# Main.net
KiCad netlist of a schematic drawn in Altium Designer
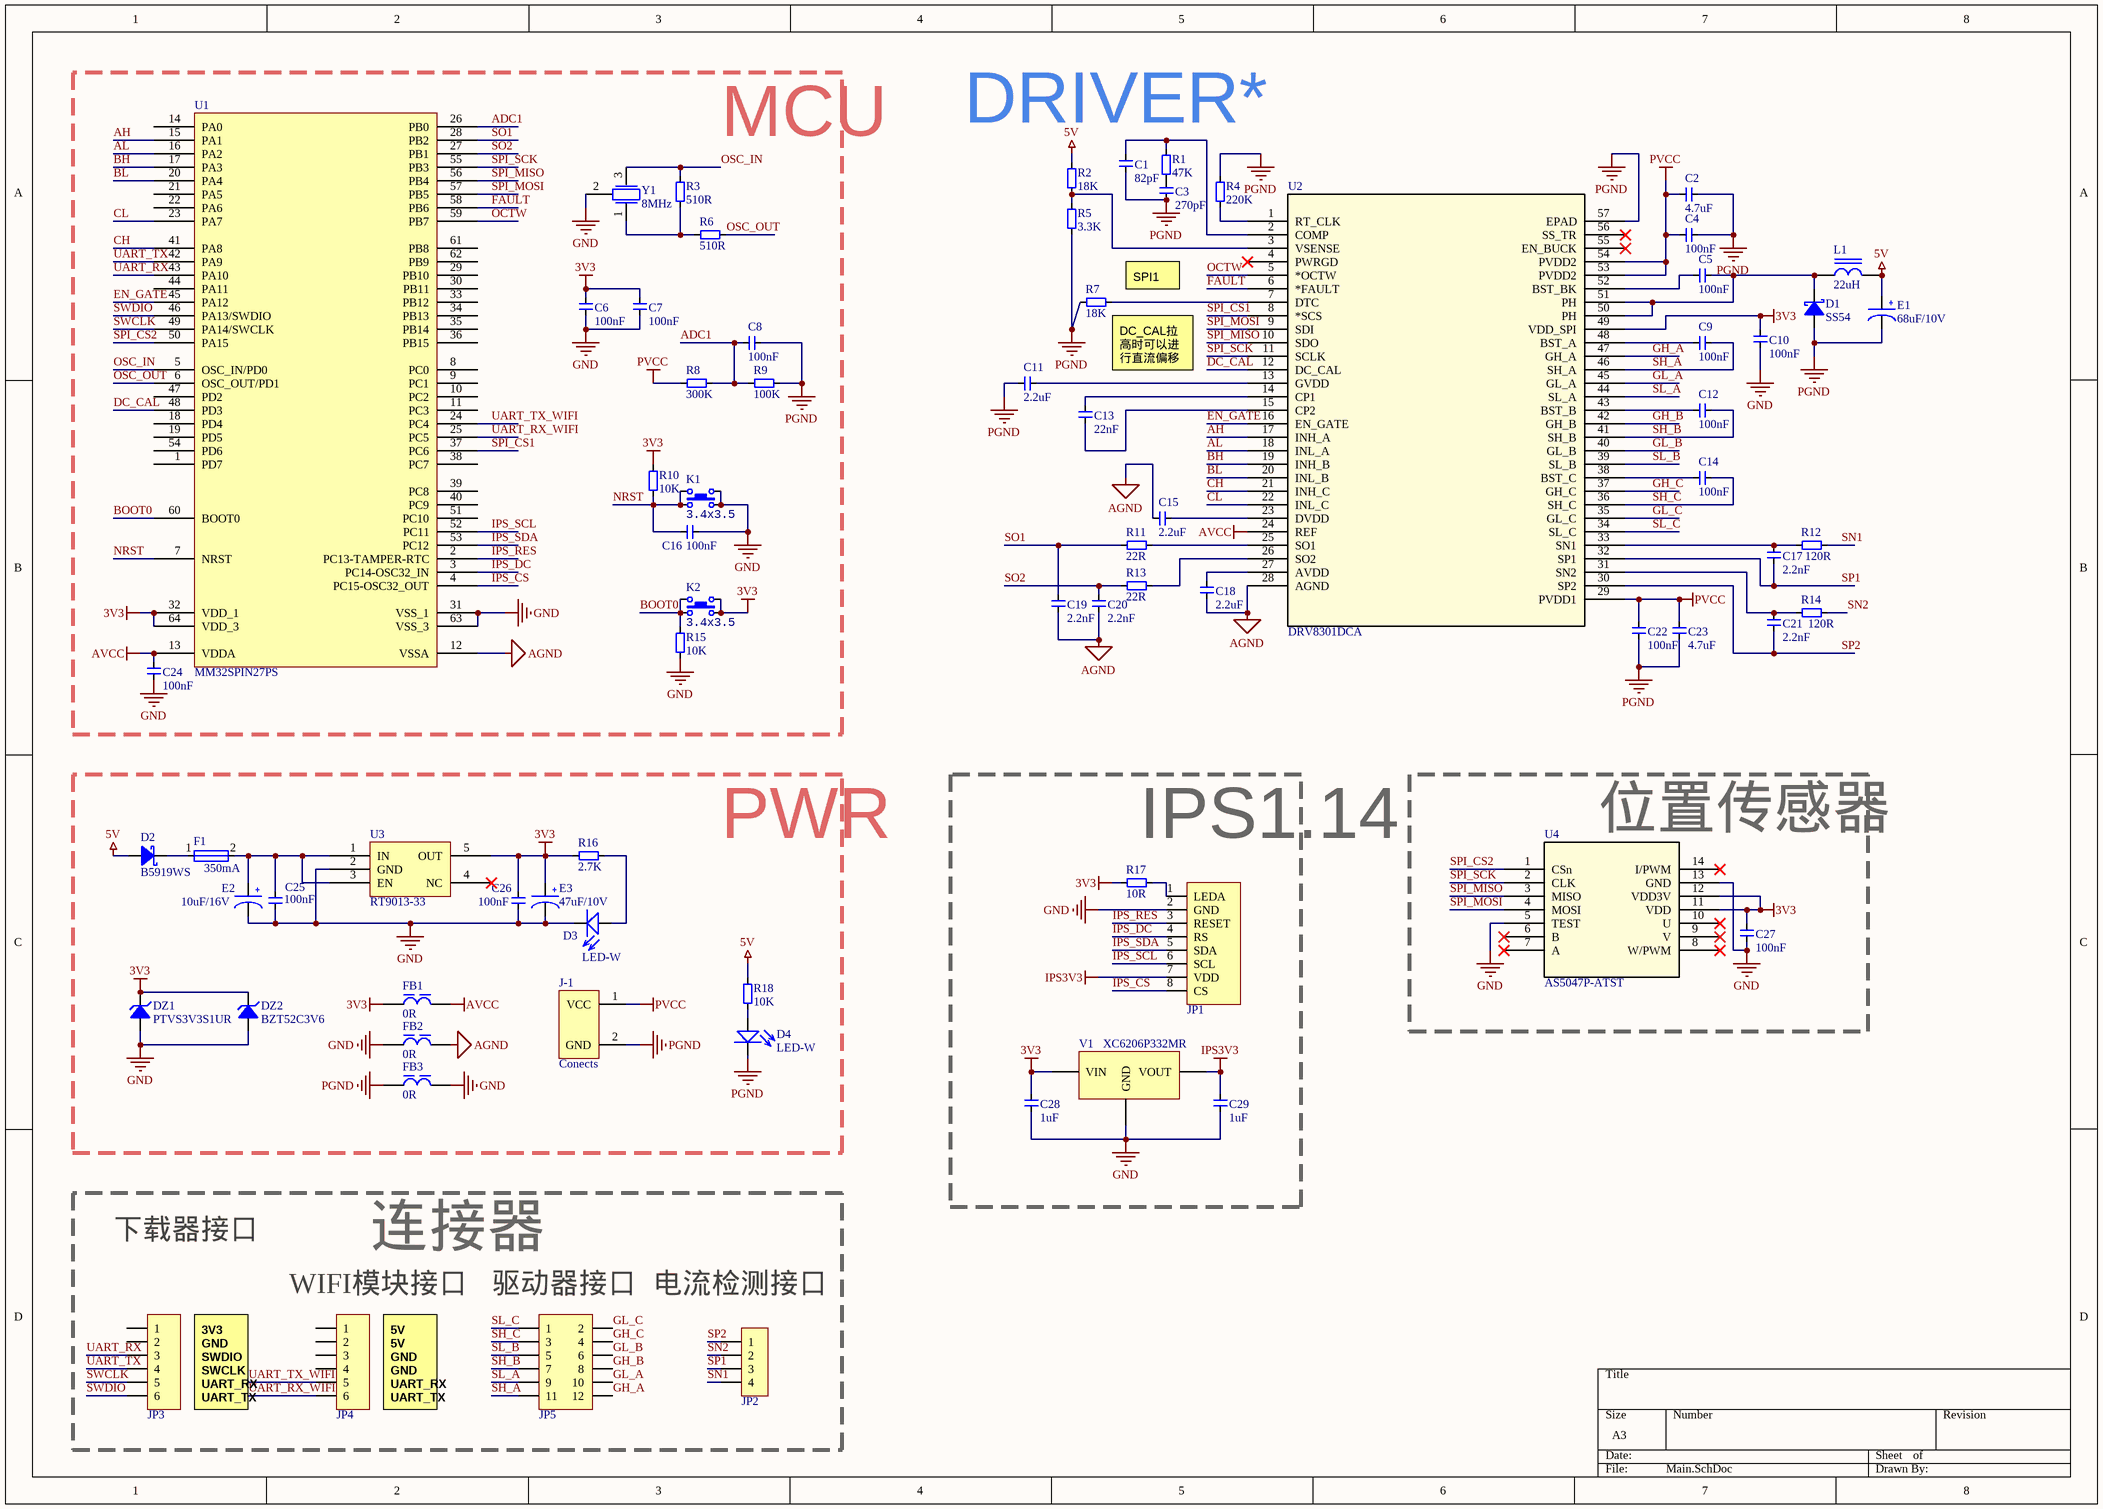
[diagram p0: Main.SchDoc]

(export (version "E")
  (design (tool "Eeschema 10.0.6"))
  (components
    (comp (ref "C1")
      (value "82pF")
      (footprint "C0402_L")
      (description "电容 ¦ 陶瓷电容")
      (fields (field (name "版权归属") "源创客"))
      (libsource (lib "total_lib") (part "C"))
    )
    (comp (ref "C2")
      (value "4.7uF")
      (footprint "C0603_L")
      (description "电容 ¦ 陶瓷电容")
      (fields (field (name "版权归属") "源创客"))
      (libsource (lib "total_lib") (part "C"))
    )
    (comp (ref "C3")
      (value "270pF")
      (footprint "C0402_L")
      (description "电容 ¦ 陶瓷电容")
      (fields (field (name "版权归属") "源创客"))
      (libsource (lib "total_lib") (part "C"))
    )
    (comp (ref "C4")
      (value "100nF")
      (footprint "C0402_L")
      (description "电容 ¦ 陶瓷电容")
      (fields (field (name "版权归属") "源创客"))
      (libsource (lib "total_lib") (part "C"))
    )
    (comp (ref "C5")
      (value "100nF")
      (footprint "C0402_L")
      (description "电容 ¦ 陶瓷电容")
      (fields (field (name "版权归属") "源创客"))
      (libsource (lib "total_lib") (part "C"))
    )
    (comp (ref "C6")
      (value "100nF")
      (footprint "C0402_L")
      (description "电容 ¦ 陶瓷电容")
      (fields (field (name "版权归属") "源创客"))
      (libsource (lib "total_lib") (part "C"))
    )
    (comp (ref "C7")
      (value "100nF")
      (footprint "C0402_L")
      (description "电容 ¦ 陶瓷电容")
      (fields (field (name "版权归属") "源创客"))
      (libsource (lib "total_lib") (part "C"))
    )
    (comp (ref "C8")
      (value "100nF")
      (footprint "C0402_L")
      (description "电容 ¦ 陶瓷电容")
      (fields (field (name "版权归属") "源创客"))
      (libsource (lib "total_lib") (part "C"))
    )
    (comp (ref "C9")
      (value "100nF")
      (footprint "C0402_L")
      (description "电容 ¦ 陶瓷电容")
      (fields (field (name "版权归属") "源创客"))
      (libsource (lib "total_lib") (part "C"))
    )
    (comp (ref "C10")
      (value "100nF")
      (footprint "C0402_L")
      (description "电容 ¦ 陶瓷电容")
      (fields (field (name "版权归属") "源创客"))
      (libsource (lib "total_lib") (part "C"))
    )
    (comp (ref "C11")
      (value "2.2uF")
      (footprint "C0402_L")
      (description "电容 ¦ 陶瓷电容")
      (fields (field (name "版权归属") "源创客"))
      (libsource (lib "total_lib") (part "C"))
    )
    (comp (ref "C12")
      (value "100nF")
      (footprint "C0402_L")
      (description "电容 ¦ 陶瓷电容")
      (fields (field (name "版权归属") "源创客"))
      (libsource (lib "total_lib") (part "C"))
    )
    (comp (ref "C13")
      (value "22nF")
      (footprint "C0402_L")
      (description "电容 ¦ 陶瓷电容")
      (fields (field (name "版权归属") "源创客"))
      (libsource (lib "total_lib") (part "C"))
    )
    (comp (ref "C14")
      (value "100nF")
      (footprint "C0402_L")
      (description "电容 ¦ 陶瓷电容")
      (fields (field (name "版权归属") "源创客"))
      (libsource (lib "total_lib") (part "C"))
    )
    (comp (ref "C15")
      (value "2.2uF")
      (footprint "C0402_L")
      (description "电容 ¦ 陶瓷电容")
      (fields (field (name "版权归属") "源创客"))
      (libsource (lib "total_lib") (part "C"))
    )
    (comp (ref "C16")
      (value "100nF")
      (footprint "C0402_L")
      (description "电容 ¦ 陶瓷电容")
      (fields (field (name "版权归属") "源创客"))
      (libsource (lib "total_lib") (part "C"))
    )
    (comp (ref "C17")
      (value "2.2nF")
      (footprint "C0402_L")
      (description "电容 ¦ 陶瓷电容")
      (fields (field (name "版权归属") "源创客"))
      (libsource (lib "total_lib") (part "C"))
    )
    (comp (ref "C18")
      (value "2.2uF")
      (footprint "C0402_L")
      (description "电容 ¦ 陶瓷电容")
      (fields (field (name "版权归属") "源创客"))
      (libsource (lib "total_lib") (part "C"))
    )
    (comp (ref "C19")
      (value "2.2nF")
      (footprint "C0402_L")
      (description "电容 ¦ 陶瓷电容")
      (fields (field (name "版权归属") "源创客"))
      (libsource (lib "total_lib") (part "C"))
    )
    (comp (ref "C20")
      (value "2.2nF")
      (footprint "C0402_L")
      (description "电容 ¦ 陶瓷电容")
      (fields (field (name "版权归属") "源创客"))
      (libsource (lib "total_lib") (part "C"))
    )
    (comp (ref "C21")
      (value "2.2nF")
      (footprint "C0402_L")
      (description "电容 ¦ 陶瓷电容")
      (fields (field (name "版权归属") "源创客"))
      (libsource (lib "total_lib") (part "C"))
    )
    (comp (ref "C22")
      (value "100nF")
      (footprint "C0402_L")
      (description "电容 ¦ 陶瓷电容")
      (fields (field (name "版权归属") "源创客"))
      (libsource (lib "total_lib") (part "C"))
    )
    (comp (ref "C23")
      (value "4.7uF")
      (footprint "C0603_L")
      (description "电容 ¦ 陶瓷电容")
      (fields (field (name "版权归属") "源创客"))
      (libsource (lib "total_lib") (part "C"))
    )
    (comp (ref "C24")
      (value "100nF")
      (footprint "C0402_L")
      (description "电容 ¦ 陶瓷电容")
      (fields (field (name "版权归属") "源创客"))
      (libsource (lib "total_lib") (part "C"))
    )
    (comp (ref "C25")
      (value "100nF")
      (footprint "C0402_L")
      (description "电容 ¦ 陶瓷电容")
      (fields (field (name "版权归属") "源创客"))
      (libsource (lib "total_lib") (part "C"))
    )
    (comp (ref "C26")
      (value "100nF")
      (footprint "C0402_L")
      (description "电容 ¦ 陶瓷电容")
      (fields (field (name "版权归属") "源创客"))
      (libsource (lib "total_lib") (part "C"))
    )
    (comp (ref "C27")
      (value "100nF")
      (footprint "C0402_L")
      (description "电容 ¦ 陶瓷电容")
      (fields (field (name "版权归属") "源创客"))
      (libsource (lib "total_lib") (part "C"))
    )
    (comp (ref "C28")
      (value "1uF")
      (footprint "C0402_L")
      (description "电容 ¦ 陶瓷电容")
      (fields (field (name "版权归属") "源创客"))
      (libsource (lib "total_lib") (part "C"))
    )
    (comp (ref "C29")
      (value "1uF")
      (footprint "C0402_L")
      (description "电容 ¦ 陶瓷电容")
      (fields (field (name "版权归属") "源创客"))
      (libsource (lib "total_lib") (part "C"))
    )
    (comp (ref "D1")
      (value "SS54")
      (footprint "SMB")
      (description "二极管 ¦ 肖特基二极管")
      (libsource (lib "total_lib") (part "SS54"))
    )
    (comp (ref "D2")
      (value "B5919WS")
      (footprint "SOD-323")
      (description "二极管 ¦ 肖特基二极管")
      (libsource (lib "total_lib") (part "1N5819"))
    )
    (comp (ref "D3")
      (value "LED-W")
      (footprint "LED 0402")
      (description "二极管 ¦ 白色LED")
      (libsource (lib "total_lib") (part "LED-White"))
    )
    (comp (ref "D4")
      (value "LED-W")
      (footprint "LED 0402")
      (description "二极管 ¦ 白色LED")
      (libsource (lib "total_lib") (part "LED-White"))
    )
    (comp (ref "DZ1")
      (value "PTVS3V3S1UR")
      (footprint "SOD-123")
      (description "二极管 ¦ 齐纳二极管")
      (libsource (lib "total_lib") (part "PTVS3V3S1UR"))
    )
    (comp (ref "DZ2")
      (value "BZT52C3V6")
      (footprint "SOD-123")
      (description "二极管 ¦ 齐纳二极管")
      (libsource (lib "total_lib") (part "BZT52C3V6"))
    )
    (comp (ref "E1")
      (value "68uF/10V")
      (footprint "CE D(6.3*5.4)")
      (description "电容 ¦ 电解电容")
      (fields (field (name "版权归属") "源创客"))
      (libsource (lib "total_lib") (part "C-CM"))
    )
    (comp (ref "E2")
      (value "10uF/16V")
      (footprint "C_3528")
      (description "电容 ¦ 钽电容")
      (fields (field (name "版权归属") "源创客"))
      (libsource (lib "total_lib") (part "C-CD"))
    )
    (comp (ref "E3")
      (value "47uF/10V")
      (footprint "C_3528")
      (description "电容 ¦ 钽电容")
      (fields (field (name "版权归属") "源创客"))
      (libsource (lib "total_lib") (part "C-CD"))
    )
    (comp (ref "F1")
      (value "350mA")
      (footprint "R0805_L")
      (description "可复位保险丝")
      (libsource (lib "total_lib") (part "FUSE"))
    )
    (comp (ref "FB1")
      (value "0R")
      (footprint "R0603_L")
      (description "磁珠")
      (libsource (lib "total_lib") (part "FB"))
    )
    (comp (ref "FB2")
      (value "0R")
      (footprint "R0603_L")
      (description "磁珠")
      (libsource (lib "total_lib") (part "FB"))
    )
    (comp (ref "FB3")
      (value "0R")
      (footprint "R1206_L")
      (description "磁珠")
      (libsource (lib "total_lib") (part "FB"))
    )
    (comp (ref "J-1")
      (value "Conects")
      (footprint "connecter-PWR")
      (description "插接件 ¦ 电源接口")
      (fields (field (name "版权归属") "源创客"))
      (libsource (lib "total_lib") (part "Conects"))
    )
    (comp (ref "JP1")
      (value "IPS1.14")
      (footprint "IPS1.14 FPC0.5 2H-WS-8P")
      (description "显示屏 ¦ 1.14寸液晶显示屏")
      (fields (field (name "版权归属") "源创客"))
      (libsource (lib "total_lib") (part "IPS1.14"))
    )
    (comp (ref "JP2")
      (value "HDR-1X4")
      (footprint "connecter-stamps-4p")
      (description "插接件 ¦ 4P接插件")
      (libsource (lib "total_lib") (part "Header 4"))
    )
    (comp (ref "JP3")
      (value "CON-6P")
      (footprint "SH1.0-6P")
      (description "插接件 ¦ SH系列")
      (libsource (lib "total_lib") (part "SH1.0-6P"))
    )
    (comp (ref "JP4")
      (value "CON-6P")
      (footprint "SH1.0-6P")
      (description "插接件 ¦ SH系列")
      (libsource (lib "total_lib") (part "SH1.0-6P"))
    )
    (comp (ref "JP5")
      (value "Header 6X2")
      (footprint "connecter-stamps-12p")
      (description "插接件 ¦ 6*2P接插件")
      (libsource (lib "total_lib") (part "Header  6X2"))
    )
    (comp (ref "K1")
      (value "3.4x3.5")
      (footprint "ButtonTACT_3.5*3.55_90")
      (description "轻触开关 ¦ 3.4x3.5四脚")
      (fields (field (name "Comment") "TACT 4P"))
      (libsource (lib "total_lib") (part "ButtonTACT"))
    )
    (comp (ref "K2")
      (value "3.4x3.5")
      (footprint "ButtonTACT_3.5*3.55_90")
      (description "轻触开关 ¦ 3.4x3.5四脚")
      (fields (field (name "Comment") "TACT 4P"))
      (libsource (lib "total_lib") (part "ButtonTACT"))
    )
    (comp (ref "L1")
      (value "22uH")
      (footprint "NR5040")
      (description "电感 ¦ 贴片功率电感")
      (fields (field (name "版权归属") "源创客"))
      (libsource (lib "total_lib") (part "L-CD"))
    )
    (comp (ref "R1")
      (value "47K")
      (footprint "R0402_L")
      (description "电阻 ¦ 贴片电阻")
      (fields (field (name "版权归属") "源创客"))
      (libsource (lib "total_lib") (part "R"))
    )
    (comp (ref "R2")
      (value "18K")
      (footprint "R0402_L")
      (description "电阻 ¦ 贴片电阻")
      (fields (field (name "版权归属") "源创客"))
      (libsource (lib "total_lib") (part "R"))
    )
    (comp (ref "R3")
      (value "510R")
      (footprint "R0402_L")
      (description "电阻 ¦ 贴片电阻")
      (fields (field (name "版权归属") "源创客"))
      (libsource (lib "total_lib") (part "R"))
    )
    (comp (ref "R4")
      (value "220K")
      (footprint "R0402_L")
      (description "电阻 ¦ 贴片电阻")
      (fields (field (name "版权归属") "源创客"))
      (libsource (lib "total_lib") (part "R"))
    )
    (comp (ref "R5")
      (value "3.3K")
      (footprint "R0402_L")
      (description "电阻 ¦ 贴片电阻")
      (fields (field (name "版权归属") "源创客"))
      (libsource (lib "total_lib") (part "R"))
    )
    (comp (ref "R6")
      (value "510R")
      (footprint "R0402_L")
      (description "电阻 ¦ 贴片电阻")
      (fields (field (name "版权归属") "源创客"))
      (libsource (lib "total_lib") (part "R"))
    )
    (comp (ref "R7")
      (value "18K")
      (footprint "R0402_L")
      (description "电阻 ¦ 贴片电阻")
      (fields (field (name "版权归属") "源创客"))
      (libsource (lib "total_lib") (part "R"))
    )
    (comp (ref "R8")
      (value "300K")
      (footprint "R0402_L")
      (description "电阻 ¦ 贴片电阻")
      (fields (field (name "版权归属") "源创客"))
      (libsource (lib "total_lib") (part "R"))
    )
    (comp (ref "R9")
      (value "100K")
      (footprint "R0402_L")
      (description "电阻 ¦ 贴片电阻")
      (fields (field (name "版权归属") "源创客"))
      (libsource (lib "total_lib") (part "R"))
    )
    (comp (ref "R10")
      (value "10K")
      (footprint "R0402_L")
      (description "电阻 ¦ 贴片电阻")
      (fields (field (name "版权归属") "源创客"))
      (libsource (lib "total_lib") (part "R"))
    )
    (comp (ref "R11")
      (value "22R")
      (footprint "R0402_L")
      (description "电阻 ¦ 贴片电阻")
      (fields (field (name "版权归属") "源创客"))
      (libsource (lib "total_lib") (part "R"))
    )
    (comp (ref "R12")
      (value "120R")
      (footprint "R0402_L")
      (description "电阻 ¦ 贴片电阻")
      (fields (field (name "版权归属") "源创客"))
      (libsource (lib "total_lib") (part "R"))
    )
    (comp (ref "R13")
      (value "22R")
      (footprint "R0402_L")
      (description "电阻 ¦ 贴片电阻")
      (fields (field (name "版权归属") "源创客"))
      (libsource (lib "total_lib") (part "R"))
    )
    (comp (ref "R14")
      (value "120R")
      (footprint "R0402_L")
      (description "电阻 ¦ 贴片电阻")
      (fields (field (name "版权归属") "源创客"))
      (libsource (lib "total_lib") (part "R"))
    )
    (comp (ref "R15")
      (value "10K")
      (footprint "R0402_L")
      (description "电阻 ¦ 贴片电阻")
      (fields (field (name "版权归属") "源创客"))
      (libsource (lib "total_lib") (part "R"))
    )
    (comp (ref "R16")
      (value "2.7K")
      (footprint "R0402_L")
      (description "电阻 ¦ 贴片电阻")
      (fields (field (name "版权归属") "源创客"))
      (libsource (lib "total_lib") (part "R"))
    )
    (comp (ref "R17")
      (value "10R")
      (footprint "R0402_L")
      (description "电阻 ¦ 贴片电阻")
      (fields (field (name "版权归属") "源创客"))
      (libsource (lib "total_lib") (part "R"))
    )
    (comp (ref "R18")
      (value "10K")
      (footprint "R0402_L")
      (description "电阻 ¦ 贴片电阻")
      (fields (field (name "版权归属") "源创客"))
      (libsource (lib "total_lib") (part "R"))
    )
    (comp (ref "U1")
      (value "MM32SPIN27PS")
      (footprint "LQFP64 10x10_L")
      (description "MCU")
      (libsource (lib "total_lib") (part "MM32SPIN27PS"))
    )
    (comp (ref "U2")
      (value "DRV8301DCA")
      (footprint "DCA56_6P35X3P61")
      (description "No Description Available")
      (fields (field (name "COPYRIGHT") "Copyright (C) 2021 Ultra Librarian. All rights reserved."))
      (libsource (lib "total_lib") (part "DRV8301DCA"))
    )
    (comp (ref "U3")
      (value "RT9013-33")
      (footprint "SOT23-5")
      (description "IC ¦ 低压线性稳压器")
      (libsource (lib "total_lib") (part "RT9013-33"))
    )
    (comp (ref "U4")
      (value "AS5047P-ATST")
      (footprint "TSSOP-14_AMS-L")
      (description "No Description Available")
      (fields (field (name "COPYRIGHT") "Copyright (C) 2022 Ultra Librarian. All rights reserved."))
      (libsource (lib "total_lib") (part "AS5047P-ATST"))
    )
    (comp (ref "V1")
      (value "XC6206P332MR")
      (footprint "SOT23")
      (description "IC ¦ 低压线性稳压芯片")
      (fields (field (name "版权归属") "源创客"))
      (libsource (lib "total_lib") (part "XC6206P332MR"))
    )
    (comp (ref "Y1")
      (value "8MHz")
      (footprint "晶振-3P")
      (description "晶振 ¦ 村田贴片")
      (libsource (lib "total_lib") (part "晶振-3Pin"))
    )
  )
  (nets
    (net (code "1") (name "/ADC1") (class "Default")
      (node (ref "C8") (pin "2") (pinfunction "2_2") (pintype "passive"))
      (node (ref "R8") (pin "2") (pinfunction "2_2") (pintype "passive"))
      (node (ref "R9") (pin "1") (pinfunction "1_1") (pintype "passive"))
      (node (ref "U1") (pin "26") (pinfunction "PB0_26") (pintype "passive"))
    )
    (net (code "2") (name "/AH") (class "Default")
      (node (ref "U1") (pin "15") (pinfunction "PA1_15") (pintype "passive"))
      (node (ref "U2") (pin "17") (pinfunction "INH_A_17") (pintype "passive"))
    )
    (net (code "3") (name "/AL") (class "Default")
      (node (ref "U1") (pin "16") (pinfunction "PA2_16") (pintype "passive"))
      (node (ref "U2") (pin "18") (pinfunction "INL_A_18") (pintype "passive"))
    )
    (net (code "4") (name "/BH") (class "Default")
      (node (ref "U1") (pin "17") (pinfunction "PA3_17") (pintype "passive"))
      (node (ref "U2") (pin "19") (pinfunction "INH_B_19") (pintype "passive"))
    )
    (net (code "5") (name "/BL") (class "Default")
      (node (ref "U1") (pin "20") (pinfunction "PA4_20") (pintype "passive"))
      (node (ref "U2") (pin "20") (pinfunction "INL_B_20") (pintype "passive"))
    )
    (net (code "6") (name "/BOOT0") (class "Default")
      (node (ref "K2") (pin "1") (pinfunction "1_1") (pintype "passive"))
      (node (ref "K2") (pin "3") (pinfunction "3_3") (pintype "passive"))
      (node (ref "R15") (pin "1") (pinfunction "1_1") (pintype "passive"))
      (node (ref "U1") (pin "60") (pinfunction "BOOT0_60") (pintype "passive"))
    )
    (net (code "7") (name "/CH") (class "Default")
      (node (ref "U1") (pin "41") (pinfunction "PA8_41") (pintype "passive"))
      (node (ref "U2") (pin "21") (pinfunction "INH_C_21") (pintype "passive"))
    )
    (net (code "8") (name "/CL") (class "Default")
      (node (ref "U1") (pin "23") (pinfunction "PA7_23") (pintype "passive"))
      (node (ref "U2") (pin "22") (pinfunction "INL_C_22") (pintype "passive"))
    )
    (net (code "9") (name "/DC_CAL") (class "Default")
      (node (ref "U1") (pin "48") (pinfunction "PD3_48") (pintype "passive"))
      (node (ref "U2") (pin "12") (pinfunction "DC_CAL_12") (pintype "passive"))
    )
    (net (code "10") (name "/EN_GATE") (class "Default")
      (node (ref "U1") (pin "45") (pinfunction "PA12_45") (pintype "passive"))
      (node (ref "U2") (pin "16") (pinfunction "EN_GATE_16") (pintype "passive"))
    )
    (net (code "11") (name "/FAULT") (class "Default")
      (node (ref "U1") (pin "58") (pinfunction "PB6_58") (pintype "passive"))
      (node (ref "U2") (pin "6") (pinfunction "*FAULT_6") (pintype "passive"))
    )
    (net (code "12") (name "/GH_A") (class "Default")
      (node (ref "JP5") (pin "12") (pinfunction "12_12") (pintype "passive"))
      (node (ref "U2") (pin "47") (pinfunction "GH_A_47") (pintype "passive"))
    )
    (net (code "13") (name "/GH_B") (class "Default")
      (node (ref "JP5") (pin "8") (pinfunction "8_8") (pintype "passive"))
      (node (ref "U2") (pin "42") (pinfunction "GH_B_42") (pintype "passive"))
    )
    (net (code "14") (name "/GH_C") (class "Default")
      (node (ref "JP5") (pin "4") (pinfunction "4_4") (pintype "passive"))
      (node (ref "U2") (pin "37") (pinfunction "GH_C_37") (pintype "passive"))
    )
    (net (code "15") (name "/GL_A") (class "Default")
      (node (ref "JP5") (pin "10") (pinfunction "10_10") (pintype "passive"))
      (node (ref "U2") (pin "45") (pinfunction "GL_A_45") (pintype "passive"))
    )
    (net (code "16") (name "/GL_B") (class "Default")
      (node (ref "JP5") (pin "6") (pinfunction "6_6") (pintype "passive"))
      (node (ref "U2") (pin "40") (pinfunction "GL_B_40") (pintype "passive"))
    )
    (net (code "17") (name "/GL_C") (class "Default")
      (node (ref "JP5") (pin "2") (pinfunction "2_2") (pintype "passive"))
      (node (ref "U2") (pin "35") (pinfunction "GL_C_35") (pintype "passive"))
    )
    (net (code "18") (name "/IPS_CS") (class "Default")
      (node (ref "JP1") (pin "8") (pinfunction "CS_8") (pintype "passive"))
      (node (ref "U1") (pin "4") (pinfunction "PC15-OSC32_OUT_4") (pintype "passive"))
    )
    (net (code "19") (name "/IPS_DC") (class "Default")
      (node (ref "JP1") (pin "4") (pinfunction "RS_4") (pintype "passive"))
      (node (ref "U1") (pin "3") (pinfunction "PC14-OSC32_IN_3") (pintype "passive"))
    )
    (net (code "20") (name "/IPS_RES") (class "Default")
      (node (ref "JP1") (pin "3") (pinfunction "RESET_3") (pintype "passive"))
      (node (ref "U1") (pin "2") (pinfunction "PC13-TAMPER-RTC_2") (pintype "passive"))
    )
    (net (code "21") (name "/IPS_SCL") (class "Default")
      (node (ref "JP1") (pin "6") (pinfunction "SCL_6") (pintype "passive"))
      (node (ref "U1") (pin "52") (pinfunction "PC11_52") (pintype "passive"))
    )
    (net (code "22") (name "/IPS_SDA") (class "Default")
      (node (ref "JP1") (pin "5") (pinfunction "SDA_5") (pintype "passive"))
      (node (ref "U1") (pin "53") (pinfunction "PC12_53") (pintype "passive"))
    )
    (net (code "23") (name "/NRST") (class "Default")
      (node (ref "C16") (pin "1") (pinfunction "1_1") (pintype "passive"))
      (node (ref "K1") (pin "1") (pinfunction "1_1") (pintype "passive"))
      (node (ref "K1") (pin "3") (pinfunction "3_3") (pintype "passive"))
      (node (ref "R10") (pin "2") (pinfunction "2_2") (pintype "passive"))
      (node (ref "U1") (pin "7") (pinfunction "NRST_7") (pintype "passive"))
    )
    (net (code "24") (name "/OCTW") (class "Default")
      (node (ref "U1") (pin "59") (pinfunction "PB7_59") (pintype "passive"))
      (node (ref "U2") (pin "5") (pinfunction "*OCTW_5") (pintype "passive"))
    )
    (net (code "25") (name "/OSC_IN") (class "Default")
      (node (ref "R3") (pin "2") (pinfunction "2_2") (pintype "passive"))
      (node (ref "U1") (pin "5") (pinfunction "OSC_IN/PD0_5") (pintype "passive"))
      (node (ref "Y1") (pin "3") (pinfunction "3_3") (pintype "passive"))
    )
    (net (code "26") (name "/OSC_OUT") (class "Default")
      (node (ref "R6") (pin "2") (pinfunction "2_2") (pintype "passive"))
      (node (ref "U1") (pin "6") (pinfunction "OSC_OUT/PD1_6") (pintype "passive"))
    )
    (net (code "27") (name "/SH_A") (class "Default")
      (node (ref "C9") (pin "1") (pinfunction "1_1") (pintype "passive"))
      (node (ref "JP5") (pin "11") (pinfunction "11_11") (pintype "passive"))
      (node (ref "U2") (pin "46") (pinfunction "SH_A_46") (pintype "passive"))
    )
    (net (code "28") (name "/SH_B") (class "Default")
      (node (ref "C12") (pin "1") (pinfunction "1_1") (pintype "passive"))
      (node (ref "JP5") (pin "7") (pinfunction "7_7") (pintype "passive"))
      (node (ref "U2") (pin "41") (pinfunction "SH_B_41") (pintype "passive"))
    )
    (net (code "29") (name "/SH_C") (class "Default")
      (node (ref "C14") (pin "1") (pinfunction "1_1") (pintype "passive"))
      (node (ref "JP5") (pin "3") (pinfunction "3_3") (pintype "passive"))
      (node (ref "U2") (pin "36") (pinfunction "SH_C_36") (pintype "passive"))
    )
    (net (code "30") (name "/SL_A") (class "Default")
      (node (ref "JP5") (pin "9") (pinfunction "9_9") (pintype "passive"))
      (node (ref "U2") (pin "44") (pinfunction "SL_A_44") (pintype "passive"))
    )
    (net (code "31") (name "/SL_B") (class "Default")
      (node (ref "JP5") (pin "5") (pinfunction "5_5") (pintype "passive"))
      (node (ref "U2") (pin "39") (pinfunction "SL_B_39") (pintype "passive"))
    )
    (net (code "32") (name "/SL_C") (class "Default")
      (node (ref "JP5") (pin "1") (pinfunction "1_1") (pintype "passive"))
      (node (ref "U2") (pin "34") (pinfunction "SL_C_34") (pintype "passive"))
    )
    (net (code "33") (name "/SN1") (class "Default")
      (node (ref "JP2") (pin "4") (pinfunction "4_4") (pintype "passive"))
      (node (ref "R12") (pin "1") (pinfunction "1_1") (pintype "passive"))
    )
    (net (code "34") (name "/SN2") (class "Default")
      (node (ref "JP2") (pin "2") (pinfunction "2_2") (pintype "passive"))
      (node (ref "R14") (pin "1") (pinfunction "1_1") (pintype "passive"))
    )
    (net (code "35") (name "/SO1") (class "Default")
      (node (ref "C19") (pin "2") (pinfunction "2_2") (pintype "passive"))
      (node (ref "R11") (pin "2") (pinfunction "2_2") (pintype "passive"))
      (node (ref "U1") (pin "28") (pinfunction "PB2_28") (pintype "passive"))
    )
    (net (code "36") (name "/SO2") (class "Default")
      (node (ref "C20") (pin "2") (pinfunction "2_2") (pintype "passive"))
      (node (ref "R13") (pin "2") (pinfunction "2_2") (pintype "passive"))
      (node (ref "U1") (pin "27") (pinfunction "PB1_27") (pintype "passive"))
    )
    (net (code "37") (name "/SP1") (class "Default")
      (node (ref "C17") (pin "1") (pinfunction "1_1") (pintype "passive"))
      (node (ref "JP2") (pin "3") (pinfunction "3_3") (pintype "passive"))
      (node (ref "U2") (pin "32") (pinfunction "SP1_32") (pintype "passive"))
    )
    (net (code "38") (name "/SP2") (class "Default")
      (node (ref "C21") (pin "1") (pinfunction "1_1") (pintype "passive"))
      (node (ref "JP2") (pin "1") (pinfunction "1_1") (pintype "passive"))
      (node (ref "U2") (pin "30") (pinfunction "SP2_30") (pintype "passive"))
    )
    (net (code "39") (name "/SPI_CS1") (class "Default")
      (node (ref "U1") (pin "37") (pinfunction "PC6_37") (pintype "passive"))
      (node (ref "U2") (pin "8") (pinfunction "*SCS_8") (pintype "passive"))
    )
    (net (code "40") (name "/SPI_CS2") (class "Default")
      (node (ref "U1") (pin "50") (pinfunction "PA15_50") (pintype "passive"))
      (node (ref "U4") (pin "1") (pinfunction "CSn_1") (pintype "passive"))
    )
    (net (code "41") (name "/SPI_MISO") (class "Default")
      (node (ref "U1") (pin "56") (pinfunction "PB4_56") (pintype "passive"))
      (node (ref "U2") (pin "10") (pinfunction "SDO_10") (pintype "passive"))
      (node (ref "U4") (pin "3") (pinfunction "MISO_3") (pintype "passive"))
    )
    (net (code "42") (name "/SPI_MOSI") (class "Default")
      (node (ref "U1") (pin "57") (pinfunction "PB5_57") (pintype "passive"))
      (node (ref "U2") (pin "9") (pinfunction "SDI_9") (pintype "passive"))
      (node (ref "U4") (pin "4") (pinfunction "MOSI_4") (pintype "passive"))
    )
    (net (code "43") (name "/SPI_SCK") (class "Default")
      (node (ref "U1") (pin "55") (pinfunction "PB3_55") (pintype "passive"))
      (node (ref "U2") (pin "11") (pinfunction "SCLK_11") (pintype "passive"))
      (node (ref "U4") (pin "2") (pinfunction "CLK_2") (pintype "passive"))
    )
    (net (code "44") (name "/SWCLK") (class "Default")
      (node (ref "JP3") (pin "5") (pinfunction "5_5") (pintype "passive"))
      (node (ref "U1") (pin "49") (pinfunction "PA14/SWCLK_49") (pintype "passive"))
    )
    (net (code "45") (name "/SWDIO") (class "Default")
      (node (ref "JP3") (pin "6") (pinfunction "6_6") (pintype "passive"))
      (node (ref "U1") (pin "46") (pinfunction "PA13/SWDIO_46") (pintype "passive"))
    )
    (net (code "46") (name "/UART_RX") (class "Default")
      (node (ref "JP3") (pin "3") (pinfunction "3_3") (pintype "passive"))
      (node (ref "U1") (pin "43") (pinfunction "PA10_43") (pintype "passive"))
    )
    (net (code "47") (name "/UART_RX_WIFI") (class "Default")
      (node (ref "JP4") (pin "6") (pinfunction "6_6") (pintype "passive"))
      (node (ref "U1") (pin "25") (pinfunction "PC5_25") (pintype "passive"))
    )
    (net (code "48") (name "/UART_TX") (class "Default")
      (node (ref "JP3") (pin "4") (pinfunction "4_4") (pintype "passive"))
      (node (ref "U1") (pin "42") (pinfunction "PA9_42") (pintype "passive"))
    )
    (net (code "49") (name "/UART_TX_WIFI") (class "Default")
      (node (ref "JP4") (pin "5") (pinfunction "5_5") (pintype "passive"))
      (node (ref "U1") (pin "24") (pinfunction "PC4_24") (pintype "passive"))
    )
    (net (code "50") (name "3V3") (class "Default")
      (node (ref "C10") (pin "1") (pinfunction "1_1") (pintype "passive"))
      (node (ref "C26") (pin "1") (pinfunction "1_1") (pintype "passive"))
      (node (ref "C27") (pin "1") (pinfunction "1_1") (pintype "passive"))
      (node (ref "C28") (pin "2") (pinfunction "2_2") (pintype "passive"))
      (node (ref "C6") (pin "2") (pinfunction "2_2") (pintype "passive"))
      (node (ref "C7") (pin "2") (pinfunction "2_2") (pintype "passive"))
      (node (ref "DZ1") (pin "2") (pinfunction "K_2") (pintype "passive"))
      (node (ref "DZ2") (pin "2") (pinfunction "K_2") (pintype "passive"))
      (node (ref "E3") (pin "1") (pinfunction "A_1") (pintype "passive"))
      (node (ref "FB1") (pin "2") (pinfunction "2_2") (pintype "passive"))
      (node (ref "K2") (pin "2") (pinfunction "2_2") (pintype "passive"))
      (node (ref "K2") (pin "4") (pinfunction "4_4") (pintype "passive"))
      (node (ref "R10") (pin "1") (pinfunction "1_1") (pintype "passive"))
      (node (ref "R16") (pin "1") (pinfunction "1_1") (pintype "passive"))
      (node (ref "R17") (pin "2") (pinfunction "2_2") (pintype "passive"))
      (node (ref "U1") (pin "32") (pinfunction "VDD_1_32") (pintype "passive"))
      (node (ref "U1") (pin "64") (pinfunction "VDD_3_64") (pintype "passive"))
      (node (ref "U2") (pin "49") (pinfunction "VDD_SPI_49") (pintype "passive"))
      (node (ref "U3") (pin "5") (pinfunction "OUT_5") (pintype "passive"))
      (node (ref "U4") (pin "11") (pinfunction "VDD_11") (pintype "passive"))
      (node (ref "U4") (pin "12") (pinfunction "VDD3V_12") (pintype "passive"))
      (node (ref "V1") (pin "3") (pinfunction "VIN_3") (pintype "passive"))
    )
    (net (code "51") (name "5V") (class "Default")
      (node (ref "D2") (pin "1") (pinfunction "A_1") (pintype "passive"))
      (node (ref "E1") (pin "1") (pinfunction "A_1") (pintype "passive"))
      (node (ref "L1") (pin "2") (pinfunction "2_2") (pintype "passive"))
      (node (ref "R18") (pin "1") (pinfunction "1_1") (pintype "passive"))
      (node (ref "R2") (pin "2") (pinfunction "2_2") (pintype "passive"))
    )
    (net (code "52") (name "AGND") (class "Default")
      (node (ref "C15") (pin "1") (pinfunction "1_1") (pintype "passive"))
      (node (ref "C18") (pin "1") (pinfunction "1_1") (pintype "passive"))
      (node (ref "C19") (pin "1") (pinfunction "1_1") (pintype "passive"))
      (node (ref "C20") (pin "1") (pinfunction "1_1") (pintype "passive"))
      (node (ref "FB2") (pin "1") (pinfunction "1_1") (pintype "passive"))
      (node (ref "U1") (pin "12") (pinfunction "VSSA_12") (pintype "passive"))
      (node (ref "U2") (pin "28") (pinfunction "AGND_28") (pintype "passive"))
    )
    (net (code "53") (name "AVCC") (class "Default")
      (node (ref "C24") (pin "2") (pinfunction "2_2") (pintype "passive"))
      (node (ref "FB1") (pin "1") (pinfunction "1_1") (pintype "passive"))
      (node (ref "U1") (pin "13") (pinfunction "VDDA_13") (pintype "passive"))
      (node (ref "U2") (pin "24") (pinfunction "REF_24") (pintype "passive"))
    )
    (net (code "54") (name "GND") (class "Default")
      (node (ref "C10") (pin "2") (pinfunction "2_2") (pintype "passive"))
      (node (ref "C16") (pin "2") (pinfunction "2_2") (pintype "passive"))
      (node (ref "C24") (pin "1") (pinfunction "1_1") (pintype "passive"))
      (node (ref "C25") (pin "2") (pinfunction "2_2") (pintype "passive"))
      (node (ref "C26") (pin "2") (pinfunction "2_2") (pintype "passive"))
      (node (ref "C27") (pin "2") (pinfunction "2_2") (pintype "passive"))
      (node (ref "C28") (pin "1") (pinfunction "1_1") (pintype "passive"))
      (node (ref "C29") (pin "1") (pinfunction "1_1") (pintype "passive"))
      (node (ref "C6") (pin "1") (pinfunction "1_1") (pintype "passive"))
      (node (ref "C7") (pin "1") (pinfunction "1_1") (pintype "passive"))
      (node (ref "D3") (pin "2") (pinfunction "1_2") (pintype "passive"))
      (node (ref "DZ1") (pin "1") (pinfunction "A_1") (pintype "passive"))
      (node (ref "DZ2") (pin "1") (pinfunction "A_1") (pintype "passive"))
      (node (ref "E2") (pin "2") (pinfunction "K_2") (pintype "passive"))
      (node (ref "E3") (pin "2") (pinfunction "K_2") (pintype "passive"))
      (node (ref "FB2") (pin "2") (pinfunction "2_2") (pintype "passive"))
      (node (ref "FB3") (pin "1") (pinfunction "1_1") (pintype "passive"))
      (node (ref "JP1") (pin "2") (pinfunction "GND_2") (pintype "passive"))
      (node (ref "K1") (pin "2") (pinfunction "2_2") (pintype "passive"))
      (node (ref "K1") (pin "4") (pinfunction "4_4") (pintype "passive"))
      (node (ref "R15") (pin "2") (pinfunction "2_2") (pintype "passive"))
      (node (ref "U1") (pin "31") (pinfunction "VSS_1_31") (pintype "passive"))
      (node (ref "U1") (pin "63") (pinfunction "VSS_3_63") (pintype "passive"))
      (node (ref "U3") (pin "2") (pinfunction "GND_2") (pintype "passive"))
      (node (ref "U4") (pin "13") (pinfunction "GND_13") (pintype "passive"))
      (node (ref "U4") (pin "5") (pinfunction "TEST_5") (pintype "passive"))
      (node (ref "V1") (pin "1") (pinfunction "GND_1") (pintype "passive"))
      (node (ref "Y1") (pin "2") (pinfunction "2_2") (pintype "passive"))
    )
    (net (code "55") (name "IPS3V3") (class "Default")
      (node (ref "C29") (pin "2") (pinfunction "2_2") (pintype "passive"))
      (node (ref "JP1") (pin "7") (pinfunction "VDD_7") (pintype "passive"))
      (node (ref "V1") (pin "2") (pinfunction "VOUT_2") (pintype "passive"))
    )
    (net (code "56") (name "Net-(C3-Pad2)") (class "Default")
      (node (ref "C3") (pin "2") (pinfunction "2_2") (pintype "passive"))
      (node (ref "R1") (pin "1") (pinfunction "1_1") (pintype "passive"))
    )
    (net (code "57") (name "Net-(D1-K)") (class "Default")
      (node (ref "C5") (pin "1") (pinfunction "1_1") (pintype "passive"))
      (node (ref "D1") (pin "2") (pinfunction "K_2") (pintype "passive"))
      (node (ref "L1") (pin "1") (pinfunction "1_1") (pintype "passive"))
      (node (ref "U2") (pin "50") (pinfunction "PH_50") (pintype "passive"))
      (node (ref "U2") (pin "51") (pinfunction "PH_51") (pintype "passive"))
    )
    (net (code "58") (name "Net-(D2-K)") (class "Default")
      (node (ref "D2") (pin "2") (pinfunction "K_2") (pintype "passive"))
      (node (ref "F1") (pin "1") (pinfunction "116_1") (pintype "passive"))
    )
    (net (code "59") (name "Net-(D3-2)") (class "Default")
      (node (ref "D3") (pin "1") (pinfunction "2_1") (pintype "passive"))
      (node (ref "R16") (pin "2") (pinfunction "2_2") (pintype "passive"))
    )
    (net (code "60") (name "Net-(D4-2)") (class "Default")
      (node (ref "D4") (pin "1") (pinfunction "2_1") (pintype "passive"))
      (node (ref "R18") (pin "2") (pinfunction "2_2") (pintype "passive"))
    )
    (net (code "61") (name "Net-(E2-A)") (class "Default")
      (node (ref "C25") (pin "1") (pinfunction "1_1") (pintype "passive"))
      (node (ref "E2") (pin "1") (pinfunction "A_1") (pintype "passive"))
      (node (ref "F1") (pin "2") (pinfunction "2_2") (pintype "passive"))
      (node (ref "U3") (pin "1") (pinfunction "IN_1") (pintype "passive"))
      (node (ref "U3") (pin "3") (pinfunction "EN_3") (pintype "passive"))
    )
    (net (code "62") (name "Net-(JP1-LEDA)") (class "Default")
      (node (ref "JP1") (pin "1") (pinfunction "LEDA_1") (pintype "passive"))
      (node (ref "R17") (pin "1") (pinfunction "1_1") (pintype "passive"))
    )
    (net (code "63") (name "Net-(R3-Pad1)") (class "Default")
      (node (ref "R3") (pin "1") (pinfunction "1_1") (pintype "passive"))
      (node (ref "R6") (pin "1") (pinfunction "1_1") (pintype "passive"))
      (node (ref "Y1") (pin "1") (pinfunction "1_1") (pintype "passive"))
    )
    (net (code "64") (name "Net-(U2-AVDD)") (class "Default")
      (node (ref "C18") (pin "2") (pinfunction "2_2") (pintype "passive"))
      (node (ref "U2") (pin "27") (pinfunction "AVDD_27") (pintype "passive"))
    )
    (net (code "65") (name "Net-(U2-BST_A)") (class "Default")
      (node (ref "C9") (pin "2") (pinfunction "2_2") (pintype "passive"))
      (node (ref "U2") (pin "48") (pinfunction "BST_A_48") (pintype "passive"))
    )
    (net (code "66") (name "Net-(U2-BST_B)") (class "Default")
      (node (ref "C12") (pin "2") (pinfunction "2_2") (pintype "passive"))
      (node (ref "U2") (pin "43") (pinfunction "BST_B_43") (pintype "passive"))
    )
    (net (code "67") (name "Net-(U2-BST_BK)") (class "Default")
      (node (ref "C5") (pin "2") (pinfunction "2_2") (pintype "passive"))
      (node (ref "U2") (pin "52") (pinfunction "BST_BK_52") (pintype "passive"))
    )
    (net (code "68") (name "Net-(U2-BST_C)") (class "Default")
      (node (ref "C14") (pin "2") (pinfunction "2_2") (pintype "passive"))
      (node (ref "U2") (pin "38") (pinfunction "BST_C_38") (pintype "passive"))
    )
    (net (code "69") (name "Net-(U2-COMP)") (class "Default")
      (node (ref "C1") (pin "2") (pinfunction "2_2") (pintype "passive"))
      (node (ref "R1") (pin "2") (pinfunction "2_2") (pintype "passive"))
      (node (ref "U2") (pin "2") (pinfunction "COMP_2") (pintype "passive"))
    )
    (net (code "70") (name "Net-(U2-CP1)") (class "Default")
      (node (ref "C13") (pin "2") (pinfunction "2_2") (pintype "passive"))
      (node (ref "U2") (pin "14") (pinfunction "CP1_14") (pintype "passive"))
    )
    (net (code "71") (name "Net-(U2-CP2)") (class "Default")
      (node (ref "C13") (pin "1") (pinfunction "1_1") (pintype "passive"))
      (node (ref "U2") (pin "15") (pinfunction "CP2_15") (pintype "passive"))
    )
    (net (code "72") (name "Net-(U2-DTC)") (class "Default")
      (node (ref "R7") (pin "1") (pinfunction "1_1") (pintype "passive"))
      (node (ref "U2") (pin "7") (pinfunction "DTC_7") (pintype "passive"))
    )
    (net (code "73") (name "Net-(U2-DVDD)") (class "Default")
      (node (ref "C15") (pin "2") (pinfunction "2_2") (pintype "passive"))
      (node (ref "U2") (pin "23") (pinfunction "DVDD_23") (pintype "passive"))
    )
    (net (code "74") (name "Net-(U2-GVDD)") (class "Default")
      (node (ref "C11") (pin "2") (pinfunction "2_2") (pintype "passive"))
      (node (ref "U2") (pin "13") (pinfunction "GVDD_13") (pintype "passive"))
    )
    (net (code "75") (name "Net-(U2-RT_CLK)") (class "Default")
      (node (ref "R4") (pin "1") (pinfunction "1_1") (pintype "passive"))
      (node (ref "U2") (pin "1") (pinfunction "RT_CLK_1") (pintype "passive"))
    )
    (net (code "76") (name "Net-(U2-SN1)") (class "Default")
      (node (ref "C17") (pin "2") (pinfunction "2_2") (pintype "passive"))
      (node (ref "R12") (pin "2") (pinfunction "2_2") (pintype "passive"))
      (node (ref "U2") (pin "33") (pinfunction "SN1_33") (pintype "passive"))
    )
    (net (code "77") (name "Net-(U2-SN2)") (class "Default")
      (node (ref "C21") (pin "2") (pinfunction "2_2") (pintype "passive"))
      (node (ref "R14") (pin "2") (pinfunction "2_2") (pintype "passive"))
      (node (ref "U2") (pin "31") (pinfunction "SN2_31") (pintype "passive"))
    )
    (net (code "78") (name "Net-(U2-SO1)") (class "Default")
      (node (ref "R11") (pin "1") (pinfunction "1_1") (pintype "passive"))
      (node (ref "U2") (pin "25") (pinfunction "SO1_25") (pintype "passive"))
    )
    (net (code "79") (name "Net-(U2-SO2)") (class "Default")
      (node (ref "R13") (pin "1") (pinfunction "1_1") (pintype "passive"))
      (node (ref "U2") (pin "26") (pinfunction "SO2_26") (pintype "passive"))
    )
    (net (code "80") (name "Net-(U2-VSENSE)") (class "Default")
      (node (ref "R2") (pin "1") (pinfunction "1_1") (pintype "passive"))
      (node (ref "R5") (pin "2") (pinfunction "2_2") (pintype "passive"))
      (node (ref "U2") (pin "3") (pinfunction "VSENSE_3") (pintype "passive"))
    )
    (net (code "81") (name "PGND") (class "Default")
      (node (ref "C1") (pin "1") (pinfunction "1_1") (pintype "passive"))
      (node (ref "C11") (pin "1") (pinfunction "1_1") (pintype "passive"))
      (node (ref "C2") (pin "2") (pinfunction "2_2") (pintype "passive"))
      (node (ref "C22") (pin "1") (pinfunction "1_1") (pintype "passive"))
      (node (ref "C23") (pin "1") (pinfunction "1_1") (pintype "passive"))
      (node (ref "C3") (pin "1") (pinfunction "1_1") (pintype "passive"))
      (node (ref "C4") (pin "2") (pinfunction "2_2") (pintype "passive"))
      (node (ref "C8") (pin "1") (pinfunction "1_1") (pintype "passive"))
      (node (ref "D1") (pin "1") (pinfunction "A_1") (pintype "passive"))
      (node (ref "D4") (pin "2") (pinfunction "1_2") (pintype "passive"))
      (node (ref "E1") (pin "2") (pinfunction "K_2") (pintype "passive"))
      (node (ref "FB3") (pin "2") (pinfunction "2_2") (pintype "passive"))
      (node (ref "J-1") (pin "2") (pinfunction "GND_2") (pintype "passive"))
      (node (ref "R4") (pin "2") (pinfunction "2_2") (pintype "passive"))
      (node (ref "R5") (pin "1") (pinfunction "1_1") (pintype "passive"))
      (node (ref "R7") (pin "2") (pinfunction "2_2") (pintype "passive"))
      (node (ref "R9") (pin "2") (pinfunction "2_2") (pintype "passive"))
      (node (ref "U2") (pin "57") (pinfunction "EPAD_57") (pintype "passive"))
    )
    (net (code "82") (name "PVCC") (class "Default")
      (node (ref "C2") (pin "1") (pinfunction "1_1") (pintype "passive"))
      (node (ref "C22") (pin "2") (pinfunction "2_2") (pintype "passive"))
      (node (ref "C23") (pin "2") (pinfunction "2_2") (pintype "passive"))
      (node (ref "C4") (pin "1") (pinfunction "1_1") (pintype "passive"))
      (node (ref "J-1") (pin "1") (pinfunction "VCC_1") (pintype "passive"))
      (node (ref "R8") (pin "1") (pinfunction "1_1") (pintype "passive"))
      (node (ref "U2") (pin "29") (pinfunction "PVDD1_29") (pintype "passive"))
      (node (ref "U2") (pin "53") (pinfunction "PVDD2_53") (pintype "passive"))
      (node (ref "U2") (pin "54") (pinfunction "PVDD2_54") (pintype "passive"))
    )
    (net (code "83") (name "unconnected-(JP3-Pad1)") (class "Default")
      (node (ref "JP3") (pin "1") (pinfunction "1_1") (pintype "passive"))
    )
    (net (code "84") (name "unconnected-(JP3-Pad2)") (class "Default")
      (node (ref "JP3") (pin "2") (pinfunction "2_2") (pintype "passive"))
    )
    (net (code "85") (name "unconnected-(JP4-Pad1)") (class "Default")
      (node (ref "JP4") (pin "1") (pinfunction "1_1") (pintype "passive"))
    )
    (net (code "86") (name "unconnected-(JP4-Pad2)") (class "Default")
      (node (ref "JP4") (pin "2") (pinfunction "2_2") (pintype "passive"))
    )
    (net (code "87") (name "unconnected-(JP4-Pad3)") (class "Default")
      (node (ref "JP4") (pin "3") (pinfunction "3_3") (pintype "passive"))
    )
    (net (code "88") (name "unconnected-(JP4-Pad4)") (class "Default")
      (node (ref "JP4") (pin "4") (pinfunction "4_4") (pintype "passive"))
    )
    (net (code "89") (name "unconnected-(U1-PA0-Pad14)") (class "Default")
      (node (ref "U1") (pin "14") (pinfunction "PA0_14") (pintype "passive"))
    )
    (net (code "90") (name "unconnected-(U1-PA5-Pad21)") (class "Default")
      (node (ref "U1") (pin "21") (pinfunction "PA5_21") (pintype "passive"))
    )
    (net (code "91") (name "unconnected-(U1-PA6-Pad22)") (class "Default")
      (node (ref "U1") (pin "22") (pinfunction "PA6_22") (pintype "passive"))
    )
    (net (code "92") (name "unconnected-(U1-PA11-Pad44)") (class "Default")
      (node (ref "U1") (pin "44") (pinfunction "PA11_44") (pintype "passive"))
    )
    (net (code "93") (name "unconnected-(U1-PB8-Pad61)") (class "Default")
      (node (ref "U1") (pin "61") (pinfunction "PB8_61") (pintype "passive"))
    )
    (net (code "94") (name "unconnected-(U1-PB9-Pad62)") (class "Default")
      (node (ref "U1") (pin "62") (pinfunction "PB9_62") (pintype "passive"))
    )
    (net (code "95") (name "unconnected-(U1-PB10-Pad29)") (class "Default")
      (node (ref "U1") (pin "29") (pinfunction "PB10_29") (pintype "passive"))
    )
    (net (code "96") (name "unconnected-(U1-PB11-Pad30)") (class "Default")
      (node (ref "U1") (pin "30") (pinfunction "PB11_30") (pintype "passive"))
    )
    (net (code "97") (name "unconnected-(U1-PB12-Pad33)") (class "Default")
      (node (ref "U1") (pin "33") (pinfunction "PB12_33") (pintype "passive"))
    )
    (net (code "98") (name "unconnected-(U1-PB13-Pad34)") (class "Default")
      (node (ref "U1") (pin "34") (pinfunction "PB13_34") (pintype "passive"))
    )
    (net (code "99") (name "unconnected-(U1-PB14-Pad35)") (class "Default")
      (node (ref "U1") (pin "35") (pinfunction "PB14_35") (pintype "passive"))
    )
    (net (code "100") (name "unconnected-(U1-PB15-Pad36)") (class "Default")
      (node (ref "U1") (pin "36") (pinfunction "PB15_36") (pintype "passive"))
    )
    (net (code "101") (name "unconnected-(U1-PC0-Pad8)") (class "Default")
      (node (ref "U1") (pin "8") (pinfunction "PC0_8") (pintype "passive"))
    )
    (net (code "102") (name "unconnected-(U1-PC1-Pad9)") (class "Default")
      (node (ref "U1") (pin "9") (pinfunction "PC1_9") (pintype "passive"))
    )
    (net (code "103") (name "unconnected-(U1-PC2-Pad10)") (class "Default")
      (node (ref "U1") (pin "10") (pinfunction "PC2_10") (pintype "passive"))
    )
    (net (code "104") (name "unconnected-(U1-PC3-Pad11)") (class "Default")
      (node (ref "U1") (pin "11") (pinfunction "PC3_11") (pintype "passive"))
    )
    (net (code "105") (name "unconnected-(U1-PC7-Pad38)") (class "Default")
      (node (ref "U1") (pin "38") (pinfunction "PC7_38") (pintype "passive"))
    )
    (net (code "106") (name "unconnected-(U1-PC8-Pad39)") (class "Default")
      (node (ref "U1") (pin "39") (pinfunction "PC8_39") (pintype "passive"))
    )
    (net (code "107") (name "unconnected-(U1-PC9-Pad40)") (class "Default")
      (node (ref "U1") (pin "40") (pinfunction "PC9_40") (pintype "passive"))
    )
    (net (code "108") (name "unconnected-(U1-PC10-Pad51)") (class "Default")
      (node (ref "U1") (pin "51") (pinfunction "PC10_51") (pintype "passive"))
    )
    (net (code "109") (name "unconnected-(U1-PD2-Pad47)") (class "Default")
      (node (ref "U1") (pin "47") (pinfunction "PD2_47") (pintype "passive"))
    )
    (net (code "110") (name "unconnected-(U1-PD4-Pad18)") (class "Default")
      (node (ref "U1") (pin "18") (pinfunction "PD4_18") (pintype "passive"))
    )
    (net (code "111") (name "unconnected-(U1-PD5-Pad19)") (class "Default")
      (node (ref "U1") (pin "19") (pinfunction "PD5_19") (pintype "passive"))
    )
    (net (code "112") (name "unconnected-(U1-PD6-Pad54)") (class "Default")
      (node (ref "U1") (pin "54") (pinfunction "PD6_54") (pintype "passive"))
    )
    (net (code "113") (name "unconnected-(U1-PD7-Pad1)") (class "Default")
      (node (ref "U1") (pin "1") (pinfunction "PD7_1") (pintype "passive"))
    )
    (net (code "114") (name "unconnected-(U2-EN_BUCK-Pad55)") (class "Default")
      (node (ref "U2") (pin "55") (pinfunction "EN_BUCK_55") (pintype "passive+no_connect"))
    )
    (net (code "115") (name "unconnected-(U2-PWRGD-Pad4)") (class "Default")
      (node (ref "U2") (pin "4") (pinfunction "PWRGD_4") (pintype "passive+no_connect"))
    )
    (net (code "116") (name "unconnected-(U2-SS_TR-Pad56)") (class "Default")
      (node (ref "U2") (pin "56") (pinfunction "SS_TR_56") (pintype "passive+no_connect"))
    )
    (net (code "117") (name "unconnected-(U3-NC-Pad4)") (class "Default")
      (node (ref "U3") (pin "4") (pinfunction "NC_4") (pintype "passive+no_connect"))
    )
    (net (code "118") (name "unconnected-(U4-A-Pad7)") (class "Default")
      (node (ref "U4") (pin "7") (pinfunction "A_7") (pintype "passive+no_connect"))
    )
    (net (code "119") (name "unconnected-(U4-B-Pad6)") (class "Default")
      (node (ref "U4") (pin "6") (pinfunction "B_6") (pintype "passive+no_connect"))
    )
    (net (code "120") (name "unconnected-(U4-I{slash}PWM-Pad14)") (class "Default")
      (node (ref "U4") (pin "14") (pinfunction "I/PWM_14") (pintype "passive+no_connect"))
    )
    (net (code "121") (name "unconnected-(U4-U-Pad10)") (class "Default")
      (node (ref "U4") (pin "10") (pinfunction "U_10") (pintype "passive+no_connect"))
    )
    (net (code "122") (name "unconnected-(U4-V-Pad9)") (class "Default")
      (node (ref "U4") (pin "9") (pinfunction "V_9") (pintype "passive+no_connect"))
    )
    (net (code "123") (name "unconnected-(U4-W{slash}PWM-Pad8)") (class "Default")
      (node (ref "U4") (pin "8") (pinfunction "W/PWM_8") (pintype "passive+no_connect"))
    )
  )
)
